# CORE.net
KiCad netlist of a schematic drawn in Altium Designer
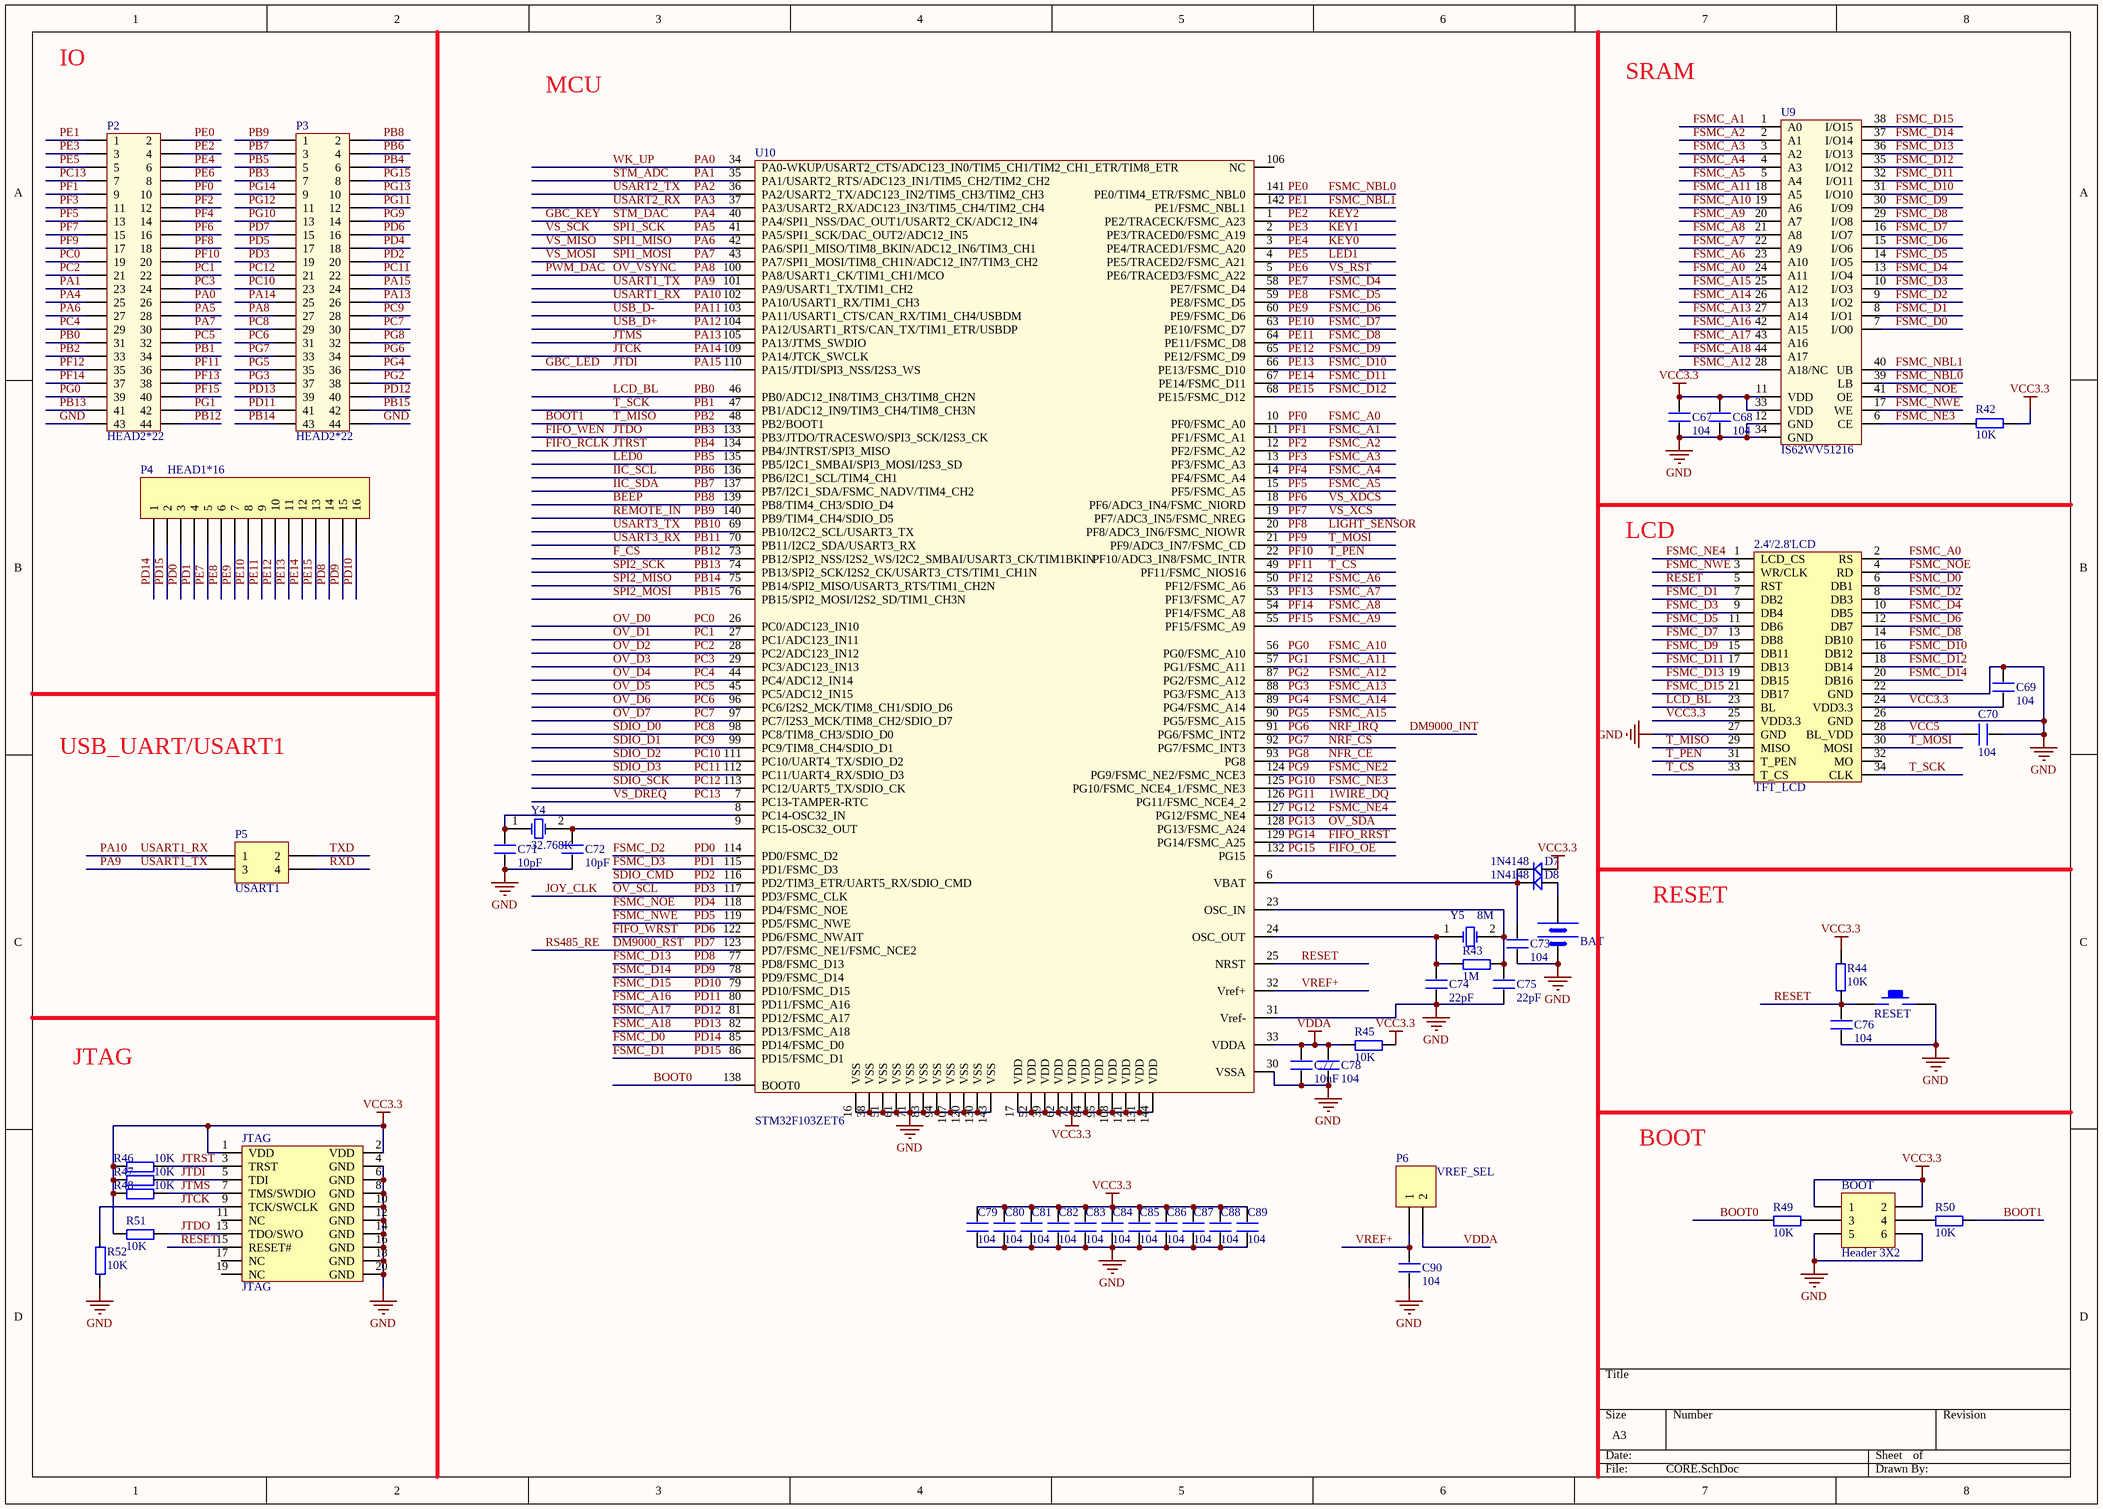
[diagram p0: CORE.SchDoc]

(export (version "E")
  (design (tool "Eeschema 10.0.6"))
  (components
    (comp (ref "2.4'/2.8'LCD")
      (value "TFT_LCD")
      (footprint "db2*17-4.3")
      (libsource (lib "WarShip V3 STM32103封装库") (part "TFT_LCD"))
    )
    (comp (ref "BAT")
      (value "BATT")
      (footprint "BATM")
      (libsource (lib "WarShip V3 STM32103封装库") (part "BAT"))
    )
    (comp (ref "BOOT")
      (value "Header 3X2")
      (footprint "HDR2X3")
      (description "Header, 3-Pin, Dual row")
      (fields (field (name "PUBLISHER") "Altium Limited"))
      (libsource (lib "WarShip V3 STM32103封装库") (part "Header 3X2"))
    )
    (comp (ref "C67") (value "104") (footprint "0603P") (libsource (lib "WarShip V3 STM32103封装库") (part "C")))
    (comp (ref "C68") (value "104") (footprint "0603P") (libsource (lib "WarShip V3 STM32103封装库") (part "C")))
    (comp (ref "C69") (value "104") (footprint "0603P") (libsource (lib "WarShip V3 STM32103封装库") (part "C")))
    (comp (ref "C70") (value "104") (footprint "0603P") (libsource (lib "WarShip V3 STM32103封装库") (part "C")))
    (comp (ref "C71")
      (value "10pF")
      (footprint "0603P")
      (libsource (lib "WarShip V3 STM32103封装库") (part "C"))
    )
    (comp (ref "C72")
      (value "10pF")
      (footprint "0603P")
      (libsource (lib "WarShip V3 STM32103封装库") (part "C"))
    )
    (comp (ref "C73") (value "104") (footprint "0603P") (libsource (lib "WarShip V3 STM32103封装库") (part "C")))
    (comp (ref "C74")
      (value "22pF")
      (footprint "0603P")
      (libsource (lib "WarShip V3 STM32103封装库") (part "C"))
    )
    (comp (ref "C75")
      (value "22pF")
      (footprint "0603P")
      (libsource (lib "WarShip V3 STM32103封装库") (part "C"))
    )
    (comp (ref "C76") (value "104") (footprint "0603P") (libsource (lib "WarShip V3 STM32103封装库") (part "C")))
    (comp (ref "C77")
      (value "10uF")
      (footprint "0603P")
      (libsource (lib "WarShip V3 STM32103封装库") (part "C"))
    )
    (comp (ref "C78") (value "104") (footprint "0603P") (libsource (lib "WarShip V3 STM32103封装库") (part "C")))
    (comp (ref "C79") (value "104") (footprint "0603P") (libsource (lib "WarShip V3 STM32103封装库") (part "C")))
    (comp (ref "C80") (value "104") (footprint "0603P") (libsource (lib "WarShip V3 STM32103封装库") (part "C")))
    (comp (ref "C81") (value "104") (footprint "0603P") (libsource (lib "WarShip V3 STM32103封装库") (part "C")))
    (comp (ref "C82") (value "104") (footprint "0603P") (libsource (lib "WarShip V3 STM32103封装库") (part "C")))
    (comp (ref "C83") (value "104") (footprint "0603P") (libsource (lib "WarShip V3 STM32103封装库") (part "C")))
    (comp (ref "C84") (value "104") (footprint "0603P") (libsource (lib "WarShip V3 STM32103封装库") (part "C")))
    (comp (ref "C85") (value "104") (footprint "0603P") (libsource (lib "WarShip V3 STM32103封装库") (part "C")))
    (comp (ref "C86") (value "104") (footprint "0603P") (libsource (lib "WarShip V3 STM32103封装库") (part "C")))
    (comp (ref "C87") (value "104") (footprint "0603P") (libsource (lib "WarShip V3 STM32103封装库") (part "C")))
    (comp (ref "C88") (value "104") (footprint "0603P") (libsource (lib "WarShip V3 STM32103封装库") (part "C")))
    (comp (ref "C89") (value "104") (footprint "0603P") (libsource (lib "WarShip V3 STM32103封装库") (part "C")))
    (comp (ref "C90") (value "104") (footprint "0603P") (libsource (lib "WarShip V3 STM32103封装库") (part "C")))
    (comp (ref "D7")
      (value "1N4148")
      (footprint "DIODE_SOP")
      (libsource (lib "WarShip V3 STM32103封装库") (part "D"))
    )
    (comp (ref "D8")
      (value "1N4148")
      (footprint "DIODE_SOP")
      (libsource (lib "WarShip V3 STM32103封装库") (part "D"))
    )
    (comp (ref "JTAG")
      (value "JTAG")
      (footprint "JTAG_20")
      (libsource (lib "WarShip V3 STM32103封装库") (part "JTAG"))
    )
    (comp (ref "P2")
      (value "HEAD2*22")
      (footprint "HEAD2*22")
      (libsource (lib "WarShip V3 STM32103封装库") (part "HEAD2*22"))
    )
    (comp (ref "P3")
      (value "HEAD2*22")
      (footprint "HEAD2*22")
      (libsource (lib "WarShip V3 STM32103封装库") (part "HEAD2*22"))
    )
    (comp (ref "P4")
      (value "HEAD1*16")
      (footprint "HDR1X16")
      (description "Header, 16-Pin")
      (fields (field (name "PUBLISHER") "Altium Limited"))
      (libsource (lib "WarShip V3 STM32103封装库") (part "Header 16"))
    )
    (comp (ref "P5")
      (value "USART1")
      (footprint "HDR2X2")
      (description "Header, 2-Pin, Dual row")
      (fields (field (name "PUBLISHER") "Altium Limited"))
      (libsource (lib "WarShip V3 STM32103封装库") (part "Header 2X2"))
    )
    (comp (ref "P6")
      (value "VREF_SEL")
      (footprint "HDR1X2")
      (description "Header, 2-Pin")
      (fields (field (name "PUBLISHER") "Altium Limited"))
      (libsource (lib "WarShip V3 STM32103封装库") (part "Header 2"))
    )
    (comp (ref "R42") (value "10K") (footprint "0603P") (libsource (lib "WarShip V3 STM32103封装库") (part "R")))
    (comp (ref "R43") (value "1M") (footprint "0603P") (libsource (lib "WarShip V3 STM32103封装库") (part "R")))
    (comp (ref "R44") (value "10K") (footprint "0603P") (libsource (lib "WarShip V3 STM32103封装库") (part "R")))
    (comp (ref "R45") (value "10K") (footprint "0603P") (libsource (lib "WarShip V3 STM32103封装库") (part "R")))
    (comp (ref "R46") (value "10K") (footprint "0603P") (libsource (lib "WarShip V3 STM32103封装库") (part "R")))
    (comp (ref "R47") (value "10K") (footprint "0603P") (libsource (lib "WarShip V3 STM32103封装库") (part "R")))
    (comp (ref "R48") (value "10K") (footprint "0603P") (libsource (lib "WarShip V3 STM32103封装库") (part "R")))
    (comp (ref "R49") (value "10K") (footprint "0603P") (libsource (lib "WarShip V3 STM32103封装库") (part "R")))
    (comp (ref "R50") (value "10K") (footprint "0603P") (libsource (lib "WarShip V3 STM32103封装库") (part "R")))
    (comp (ref "R51") (value "10K") (footprint "0603P") (libsource (lib "WarShip V3 STM32103封装库") (part "R")))
    (comp (ref "R52") (value "10K") (footprint "0603P") (libsource (lib "WarShip V3 STM32103封装库") (part "R")))
    (comp (ref "RESET")
      (value "KEY_M")
      (footprint "KEY_M")
      (libsource (lib "WarShip V3 STM32103封装库") (part "KEY_M"))
    )
    (comp (ref "U9")
      (value "IS62WV51216")
      (footprint "TSOP44")
      (libsource (lib "WarShip V3 STM32103封装库") (part "IS61LV51216"))
    )
    (comp (ref "U10")
      (value "STM32F103ZET6")
      (footprint "LQFP144")
      (libsource (lib "WarShip V3 STM32103封装库") (part "STM32F103ZET6"))
    )
    (comp (ref "Y4")
      (value "32.768K")
      (footprint "XTAL_US")
      (description "Crystal Oscillator")
      (fields (field (name "PUBLISHER") "Altium Limited"))
      (libsource (lib "WarShip V3 STM32103封装库") (part "XTAL"))
    )
    (comp (ref "Y5")
      (value "8M")
      (footprint "XTAL_US")
      (description "Crystal Oscillator")
      (fields (field (name "PUBLISHER") "Altium Limited"))
      (libsource (lib "WarShip V3 STM32103封装库") (part "XTAL"))
    )
  )
  (nets
    (net (code "1") (name "/1WIRE_DQ") (class "Default")
      (node (ref "P3") (pin "12") (pinfunction "12_12") (pintype "passive"))
      (node (ref "U10") (pin "126") (pinfunction "PG11/FSMC_NCE4_2_126") (pintype "passive"))
    )
    (net (code "2") (name "/BEEP") (class "Default")
      (node (ref "P3") (pin "2") (pinfunction "2_2") (pintype "passive"))
      (node (ref "U10") (pin "139") (pinfunction "PB8/TIM4_CH3/SDIO_D4_139") (pintype "passive"))
    )
    (net (code "3") (name "/BOOT0") (class "Default")
      (node (ref "R49") (pin "1") (pintype "passive"))
      (node (ref "U10") (pin "138") (pinfunction "BOOT0_138") (pintype "passive"))
    )
    (net (code "4") (name "/BOOT1") (class "Default")
      (node (ref "2.4'/2.8'LCD") (pin "29") (pinfunction "MISO_29") (pintype "passive"))
      (node (ref "P2") (pin "33") (pinfunction "33_33") (pintype "passive"))
      (node (ref "R50") (pin "2") (pintype "passive"))
      (node (ref "U10") (pin "48") (pinfunction "PB2/BOOT1_48") (pintype "passive"))
    )
    (net (code "5") (name "/DM9000_INT") (class "Default")
      (node (ref "P3") (pin "34") (pinfunction "34_34") (pintype "passive"))
      (node (ref "U10") (pin "91") (pinfunction "PG6/FSMC_INT2_91") (pintype "passive"))
    )
    (net (code "6") (name "/DM9000_RST") (class "Default")
      (node (ref "P3") (pin "15") (pinfunction "15_15") (pintype "passive"))
      (node (ref "U10") (pin "123") (pinfunction "PD7/FSMC_NE1/FSMC_NCE2_123") (pintype "passive"))
    )
    (net (code "7") (name "/FIFO_OE") (class "Default")
      (node (ref "P3") (pin "8") (pinfunction "8_8") (pintype "passive"))
      (node (ref "U10") (pin "132") (pinfunction "PG15_132") (pintype "passive"))
    )
    (net (code "8") (name "/FIFO_RCLK") (class "Default")
      (node (ref "JTAG") (pin "3") (pinfunction "TRST_3") (pintype "passive"))
      (node (ref "P3") (pin "6") (pinfunction "6_6") (pintype "passive"))
      (node (ref "R46") (pin "2") (pintype "passive"))
      (node (ref "U10") (pin "134") (pinfunction "PB4/JNTRST/SPI3_MISO_134") (pintype "passive"))
    )
    (net (code "9") (name "/FIFO_RRST") (class "Default")
      (node (ref "P3") (pin "9") (pinfunction "9_9") (pintype "passive"))
      (node (ref "U10") (pin "129") (pinfunction "PG14/FSMC_A25_129") (pintype "passive"))
    )
    (net (code "10") (name "/FIFO_WEN") (class "Default")
      (node (ref "JTAG") (pin "13") (pinfunction "TDO/SWO_13") (pintype "passive"))
      (node (ref "P3") (pin "7") (pinfunction "7_7") (pintype "passive"))
      (node (ref "R51") (pin "2") (pintype "passive"))
      (node (ref "U10") (pin "133") (pinfunction "PB3/JTDO/TRACESWO/SPI3_SCK/I2S3_CK_133") (pintype "passive"))
    )
    (net (code "11") (name "/FIFO_WRST") (class "Default")
      (node (ref "P3") (pin "16") (pinfunction "16_16") (pintype "passive"))
      (node (ref "U10") (pin "122") (pinfunction "PD6/FSMC_NWAIT_122") (pintype "passive"))
    )
    (net (code "12") (name "/FSMC_A0") (class "Default")
      (node (ref "2.4'/2.8'LCD") (pin "2") (pinfunction "RS_2") (pintype "passive"))
      (node (ref "P2") (pin "10") (pinfunction "10_10") (pintype "passive"))
      (node (ref "U10") (pin "10") (pinfunction "PF0/FSMC_A0_10") (pintype "passive"))
      (node (ref "U9") (pin "24") (pinfunction "A11_24") (pintype "passive"))
    )
    (net (code "13") (name "/FSMC_A1") (class "Default")
      (node (ref "P2") (pin "9") (pinfunction "9_9") (pintype "passive"))
      (node (ref "U10") (pin "11") (pinfunction "PF1/FSMC_A1_11") (pintype "passive"))
      (node (ref "U9") (pin "1") (pinfunction "A0_1") (pintype "passive"))
    )
    (net (code "14") (name "/FSMC_A2") (class "Default")
      (node (ref "P2") (pin "12") (pinfunction "12_12") (pintype "passive"))
      (node (ref "U10") (pin "12") (pinfunction "PF2/FSMC_A2_12") (pintype "passive"))
      (node (ref "U9") (pin "2") (pinfunction "A1_2") (pintype "passive"))
    )
    (net (code "15") (name "/FSMC_A3") (class "Default")
      (node (ref "P2") (pin "11") (pinfunction "11_11") (pintype "passive"))
      (node (ref "U10") (pin "13") (pinfunction "PF3/FSMC_A3_13") (pintype "passive"))
      (node (ref "U9") (pin "3") (pinfunction "A2_3") (pintype "passive"))
    )
    (net (code "16") (name "/FSMC_A4") (class "Default")
      (node (ref "P2") (pin "14") (pinfunction "14_14") (pintype "passive"))
      (node (ref "U10") (pin "14") (pinfunction "PF4/FSMC_A4_14") (pintype "passive"))
      (node (ref "U9") (pin "4") (pinfunction "A3_4") (pintype "passive"))
    )
    (net (code "17") (name "/FSMC_A5") (class "Default")
      (node (ref "P2") (pin "13") (pinfunction "13_13") (pintype "passive"))
      (node (ref "U10") (pin "15") (pinfunction "PF5/FSMC_A5_15") (pintype "passive"))
      (node (ref "U9") (pin "5") (pinfunction "A4_5") (pintype "passive"))
    )
    (net (code "18") (name "/FSMC_A6") (class "Default")
      (node (ref "P2") (pin "35") (pinfunction "35_35") (pintype "passive"))
      (node (ref "U10") (pin "50") (pinfunction "PF12/FSMC_A6_50") (pintype "passive"))
      (node (ref "U9") (pin "23") (pinfunction "A10_23") (pintype "passive"))
    )
    (net (code "19") (name "/FSMC_A7") (class "Default")
      (node (ref "P2") (pin "38") (pinfunction "38_38") (pintype "passive"))
      (node (ref "U10") (pin "53") (pinfunction "PF13/FSMC_A7_53") (pintype "passive"))
      (node (ref "U9") (pin "22") (pinfunction "A9_22") (pintype "passive"))
    )
    (net (code "20") (name "/FSMC_A8") (class "Default")
      (node (ref "P2") (pin "37") (pinfunction "37_37") (pintype "passive"))
      (node (ref "U10") (pin "54") (pinfunction "PF14/FSMC_A8_54") (pintype "passive"))
      (node (ref "U9") (pin "21") (pinfunction "A8_21") (pintype "passive"))
    )
    (net (code "21") (name "/FSMC_A9") (class "Default")
      (node (ref "P2") (pin "40") (pinfunction "40_40") (pintype "passive"))
      (node (ref "U10") (pin "55") (pinfunction "PF15/FSMC_A9_55") (pintype "passive"))
      (node (ref "U9") (pin "20") (pinfunction "A7_20") (pintype "passive"))
    )
    (net (code "22") (name "/FSMC_A10") (class "Default")
      (node (ref "P2") (pin "39") (pinfunction "39_39") (pintype "passive"))
      (node (ref "U10") (pin "56") (pinfunction "PG0/FSMC_A10_56") (pintype "passive"))
      (node (ref "U9") (pin "19") (pinfunction "A6_19") (pintype "passive"))
    )
    (net (code "23") (name "/FSMC_A11") (class "Default")
      (node (ref "P2") (pin "42") (pinfunction "42_42") (pintype "passive"))
      (node (ref "U10") (pin "57") (pinfunction "PG1/FSMC_A11_57") (pintype "passive"))
      (node (ref "U9") (pin "18") (pinfunction "A5_18") (pintype "passive"))
    )
    (net (code "24") (name "/FSMC_A12") (class "Default")
      (node (ref "P3") (pin "38") (pinfunction "38_38") (pintype "passive"))
      (node (ref "U10") (pin "87") (pinfunction "PG2/FSMC_A12_87") (pintype "passive"))
      (node (ref "U9") (pin "28") (pinfunction "A18/NC_28") (pintype "passive"))
    )
    (net (code "25") (name "/FSMC_A13") (class "Default")
      (node (ref "P3") (pin "37") (pinfunction "37_37") (pintype "passive"))
      (node (ref "U10") (pin "88") (pinfunction "PG3/FSMC_A13_88") (pintype "passive"))
      (node (ref "U9") (pin "27") (pinfunction "A14_27") (pintype "passive"))
    )
    (net (code "26") (name "/FSMC_A14") (class "Default")
      (node (ref "P3") (pin "36") (pinfunction "36_36") (pintype "passive"))
      (node (ref "U10") (pin "89") (pinfunction "PG4/FSMC_A14_89") (pintype "passive"))
      (node (ref "U9") (pin "26") (pinfunction "A13_26") (pintype "passive"))
    )
    (net (code "27") (name "/FSMC_A15") (class "Default")
      (node (ref "P3") (pin "35") (pinfunction "35_35") (pintype "passive"))
      (node (ref "U10") (pin "90") (pinfunction "PG5/FSMC_A15_90") (pintype "passive"))
      (node (ref "U9") (pin "25") (pinfunction "A12_25") (pintype "passive"))
    )
    (net (code "28") (name "/FSMC_A16") (class "Default")
      (node (ref "P3") (pin "41") (pinfunction "41_41") (pintype "passive"))
      (node (ref "U10") (pin "80") (pinfunction "PD11/FSMC_A16_80") (pintype "passive"))
      (node (ref "U9") (pin "42") (pinfunction "A15_42") (pintype "passive"))
    )
    (net (code "29") (name "/FSMC_A17") (class "Default")
      (node (ref "P3") (pin "40") (pinfunction "40_40") (pintype "passive"))
      (node (ref "U10") (pin "81") (pinfunction "PD12/FSMC_A17_81") (pintype "passive"))
      (node (ref "U9") (pin "43") (pinfunction "A16_43") (pintype "passive"))
    )
    (net (code "30") (name "/FSMC_A18") (class "Default")
      (node (ref "P3") (pin "39") (pinfunction "39_39") (pintype "passive"))
      (node (ref "U10") (pin "82") (pinfunction "PD13/FSMC_A18_82") (pintype "passive"))
      (node (ref "U9") (pin "44") (pinfunction "A17_44") (pintype "passive"))
    )
    (net (code "31") (name "/FSMC_D0") (class "Default")
      (node (ref "2.4'/2.8'LCD") (pin "6") (pinfunction "DB1_6") (pintype "passive"))
      (node (ref "P4") (pin "1") (pinfunction "1_1") (pintype "passive"))
      (node (ref "U10") (pin "85") (pinfunction "PD14/FSMC_D0_85") (pintype "passive"))
      (node (ref "U9") (pin "7") (pinfunction "I/O0_7") (pintype "passive"))
    )
    (net (code "32") (name "/FSMC_D1") (class "Default")
      (node (ref "2.4'/2.8'LCD") (pin "7") (pinfunction "DB2_7") (pintype "passive"))
      (node (ref "P4") (pin "2") (pinfunction "2_2") (pintype "passive"))
      (node (ref "U10") (pin "86") (pinfunction "PD15/FSMC_D1_86") (pintype "passive"))
      (node (ref "U9") (pin "8") (pinfunction "I/O1_8") (pintype "passive"))
    )
    (net (code "33") (name "/FSMC_D2") (class "Default")
      (node (ref "2.4'/2.8'LCD") (pin "8") (pinfunction "DB3_8") (pintype "passive"))
      (node (ref "P4") (pin "3") (pinfunction "3_3") (pintype "passive"))
      (node (ref "U10") (pin "114") (pinfunction "PD0/FSMC_D2_114") (pintype "passive"))
      (node (ref "U9") (pin "9") (pinfunction "I/O2_9") (pintype "passive"))
    )
    (net (code "34") (name "/FSMC_D3") (class "Default")
      (node (ref "2.4'/2.8'LCD") (pin "9") (pinfunction "DB4_9") (pintype "passive"))
      (node (ref "P4") (pin "4") (pinfunction "4_4") (pintype "passive"))
      (node (ref "U10") (pin "115") (pinfunction "PD1/FSMC_D3_115") (pintype "passive"))
      (node (ref "U9") (pin "10") (pinfunction "I/O3_10") (pintype "passive"))
    )
    (net (code "35") (name "/FSMC_D4") (class "Default")
      (node (ref "2.4'/2.8'LCD") (pin "10") (pinfunction "DB5_10") (pintype "passive"))
      (node (ref "P4") (pin "5") (pinfunction "5_5") (pintype "passive"))
      (node (ref "U10") (pin "58") (pinfunction "PE7/FSMC_D4_58") (pintype "passive"))
      (node (ref "U9") (pin "13") (pinfunction "I/O4_13") (pintype "passive"))
    )
    (net (code "36") (name "/FSMC_D5") (class "Default")
      (node (ref "2.4'/2.8'LCD") (pin "11") (pinfunction "DB6_11") (pintype "passive"))
      (node (ref "P4") (pin "6") (pinfunction "6_6") (pintype "passive"))
      (node (ref "U10") (pin "59") (pinfunction "PE8/FSMC_D5_59") (pintype "passive"))
      (node (ref "U9") (pin "14") (pinfunction "I/O5_14") (pintype "passive"))
    )
    (net (code "37") (name "/FSMC_D6") (class "Default")
      (node (ref "2.4'/2.8'LCD") (pin "12") (pinfunction "DB7_12") (pintype "passive"))
      (node (ref "P4") (pin "7") (pinfunction "7_7") (pintype "passive"))
      (node (ref "U10") (pin "60") (pinfunction "PE9/FSMC_D6_60") (pintype "passive"))
      (node (ref "U9") (pin "15") (pinfunction "I/O6_15") (pintype "passive"))
    )
    (net (code "38") (name "/FSMC_D7") (class "Default")
      (node (ref "2.4'/2.8'LCD") (pin "13") (pinfunction "DB8_13") (pintype "passive"))
      (node (ref "P4") (pin "8") (pinfunction "8_8") (pintype "passive"))
      (node (ref "U10") (pin "63") (pinfunction "PE10/FSMC_D7_63") (pintype "passive"))
      (node (ref "U9") (pin "16") (pinfunction "I/O7_16") (pintype "passive"))
    )
    (net (code "39") (name "/FSMC_D8") (class "Default")
      (node (ref "2.4'/2.8'LCD") (pin "14") (pinfunction "DB10_14") (pintype "passive"))
      (node (ref "P4") (pin "9") (pinfunction "9_9") (pintype "passive"))
      (node (ref "U10") (pin "64") (pinfunction "PE11/FSMC_D8_64") (pintype "passive"))
      (node (ref "U9") (pin "29") (pinfunction "I/O8_29") (pintype "passive"))
    )
    (net (code "40") (name "/FSMC_D9") (class "Default")
      (node (ref "2.4'/2.8'LCD") (pin "15") (pinfunction "DB11_15") (pintype "passive"))
      (node (ref "P4") (pin "10") (pinfunction "10_10") (pintype "passive"))
      (node (ref "U10") (pin "65") (pinfunction "PE12/FSMC_D9_65") (pintype "passive"))
      (node (ref "U9") (pin "30") (pinfunction "I/O9_30") (pintype "passive"))
    )
    (net (code "41") (name "/FSMC_D10") (class "Default")
      (node (ref "2.4'/2.8'LCD") (pin "16") (pinfunction "DB12_16") (pintype "passive"))
      (node (ref "P4") (pin "11") (pinfunction "11_11") (pintype "passive"))
      (node (ref "U10") (pin "66") (pinfunction "PE13/FSMC_D10_66") (pintype "passive"))
      (node (ref "U9") (pin "31") (pinfunction "I/O10_31") (pintype "passive"))
    )
    (net (code "42") (name "/FSMC_D11") (class "Default")
      (node (ref "2.4'/2.8'LCD") (pin "17") (pinfunction "DB13_17") (pintype "passive"))
      (node (ref "P4") (pin "12") (pinfunction "12_12") (pintype "passive"))
      (node (ref "U10") (pin "67") (pinfunction "PE14/FSMC_D11_67") (pintype "passive"))
      (node (ref "U9") (pin "32") (pinfunction "I/O11_32") (pintype "passive"))
    )
    (net (code "43") (name "/FSMC_D12") (class "Default")
      (node (ref "2.4'/2.8'LCD") (pin "18") (pinfunction "DB14_18") (pintype "passive"))
      (node (ref "P4") (pin "13") (pinfunction "13_13") (pintype "passive"))
      (node (ref "U10") (pin "68") (pinfunction "PE15/FSMC_D12_68") (pintype "passive"))
      (node (ref "U9") (pin "35") (pinfunction "I/O12_35") (pintype "passive"))
    )
    (net (code "44") (name "/FSMC_D13") (class "Default")
      (node (ref "2.4'/2.8'LCD") (pin "19") (pinfunction "DB15_19") (pintype "passive"))
      (node (ref "P4") (pin "14") (pinfunction "14_14") (pintype "passive"))
      (node (ref "U10") (pin "77") (pinfunction "PD8/FSMC_D13_77") (pintype "passive"))
      (node (ref "U9") (pin "36") (pinfunction "I/O13_36") (pintype "passive"))
    )
    (net (code "45") (name "/FSMC_D14") (class "Default")
      (node (ref "2.4'/2.8'LCD") (pin "20") (pinfunction "DB16_20") (pintype "passive"))
      (node (ref "P4") (pin "15") (pinfunction "15_15") (pintype "passive"))
      (node (ref "U10") (pin "78") (pinfunction "PD9/FSMC_D14_78") (pintype "passive"))
      (node (ref "U9") (pin "37") (pinfunction "I/O14_37") (pintype "passive"))
    )
    (net (code "46") (name "/FSMC_D15") (class "Default")
      (node (ref "2.4'/2.8'LCD") (pin "21") (pinfunction "DB17_21") (pintype "passive"))
      (node (ref "P4") (pin "16") (pinfunction "16_16") (pintype "passive"))
      (node (ref "U10") (pin "79") (pinfunction "PD10/FSMC_D15_79") (pintype "passive"))
      (node (ref "U9") (pin "38") (pinfunction "I/O15_38") (pintype "passive"))
    )
    (net (code "47") (name "/FSMC_NBL0") (class "Default")
      (node (ref "P2") (pin "2") (pinfunction "2_2") (pintype "passive"))
      (node (ref "U10") (pin "141") (pinfunction "PE0/TIM4_ETR/FSMC_NBL0_141") (pintype "passive"))
      (node (ref "U9") (pin "39") (pinfunction "LB_39") (pintype "passive"))
    )
    (net (code "48") (name "/FSMC_NBL1") (class "Default")
      (node (ref "P2") (pin "1") (pinfunction "1_1") (pintype "passive"))
      (node (ref "U10") (pin "142") (pinfunction "PE1/FSMC_NBL1_142") (pintype "passive"))
      (node (ref "U9") (pin "40") (pinfunction "UB_40") (pintype "passive"))
    )
    (net (code "49") (name "/FSMC_NE2") (class "Default")
      (node (ref "P3") (pin "14") (pinfunction "14_14") (pintype "passive"))
      (node (ref "U10") (pin "124") (pinfunction "PG9/FSMC_NE2/FSMC_NCE3_124") (pintype "passive"))
    )
    (net (code "50") (name "/FSMC_NE3") (class "Default")
      (node (ref "P3") (pin "13") (pinfunction "13_13") (pintype "passive"))
      (node (ref "R42") (pin "2") (pintype "passive"))
      (node (ref "U10") (pin "125") (pinfunction "PG10/FSMC_NCE4_1/FSMC_NE3_125") (pintype "passive"))
      (node (ref "U9") (pin "6") (pinfunction "CE_6") (pintype "passive"))
    )
    (net (code "51") (name "/FSMC_NE4") (class "Default")
      (node (ref "2.4'/2.8'LCD") (pin "1") (pinfunction "LCD_CS_1") (pintype "passive"))
      (node (ref "P3") (pin "11") (pinfunction "11_11") (pintype "passive"))
      (node (ref "U10") (pin "127") (pinfunction "PG12/FSMC_NE4_127") (pintype "passive"))
    )
    (net (code "52") (name "/FSMC_NOE") (class "Default")
      (node (ref "2.4'/2.8'LCD") (pin "4") (pinfunction "RD_4") (pintype "passive"))
      (node (ref "P3") (pin "18") (pinfunction "18_18") (pintype "passive"))
      (node (ref "U10") (pin "118") (pinfunction "PD4/FSMC_NOE_118") (pintype "passive"))
      (node (ref "U9") (pin "41") (pinfunction "OE_41") (pintype "passive"))
    )
    (net (code "53") (name "/FSMC_NWE") (class "Default")
      (node (ref "2.4'/2.8'LCD") (pin "3") (pinfunction "WR/CLK_3") (pintype "passive"))
      (node (ref "P3") (pin "17") (pinfunction "17_17") (pintype "passive"))
      (node (ref "U10") (pin "119") (pinfunction "PD5/FSMC_NWE_119") (pintype "passive"))
      (node (ref "U9") (pin "17") (pinfunction "WE_17") (pintype "passive"))
    )
    (net (code "54") (name "/F_CS") (class "Default")
      (node (ref "P2") (pin "44") (pinfunction "44_44") (pintype "passive"))
      (node (ref "U10") (pin "73") (pinfunction "PB12/SPI2_NSS/I2S2_WS/I2C2_SMBAI/USART3_CK/TIM1BKIN_73") (pintype "passive"))
    )
    (net (code "55") (name "/GBC_KEY") (class "Default")
      (node (ref "P2") (pin "25") (pinfunction "25_25") (pintype "passive"))
      (node (ref "U10") (pin "40") (pinfunction "PA4/SPI1_NSS/DAC_OUT1/USART2_CK/ADC12_IN4_40") (pintype "passive"))
    )
    (net (code "56") (name "/GBC_LED") (class "Default")
      (node (ref "JTAG") (pin "5") (pinfunction "TDI_5") (pintype "passive"))
      (node (ref "P3") (pin "24") (pinfunction "24_24") (pintype "passive"))
      (node (ref "R47") (pin "2") (pintype "passive"))
      (node (ref "U10") (pin "110") (pinfunction "PA15/JTDI/SPI3_NSS/I2S3_WS_110") (pintype "passive"))
    )
    (net (code "57") (name "/IIC_SCL") (class "Default")
      (node (ref "P3") (pin "4") (pinfunction "4_4") (pintype "passive"))
      (node (ref "U10") (pin "136") (pinfunction "PB6/I2C1_SCL/TIM4_CH1_136") (pintype "passive"))
    )
    (net (code "58") (name "/IIC_SDA") (class "Default")
      (node (ref "P3") (pin "3") (pinfunction "3_3") (pintype "passive"))
      (node (ref "U10") (pin "137") (pinfunction "PB7/I2C1_SDA/FSMC_NADV/TIM4_CH2_137") (pintype "passive"))
    )
    (net (code "59") (name "/JOY_CLK") (class "Default")
      (node (ref "P3") (pin "19") (pinfunction "19_19") (pintype "passive"))
      (node (ref "U10") (pin "117") (pinfunction "PD3/FSMC_CLK_117") (pintype "passive"))
    )
    (net (code "60") (name "/JTCK") (class "Default")
      (node (ref "JTAG") (pin "9") (pinfunction "TCK/SWCLK_9") (pintype "passive"))
      (node (ref "P3") (pin "25") (pinfunction "25_25") (pintype "passive"))
      (node (ref "R52") (pin "2") (pintype "passive"))
      (node (ref "U10") (pin "109") (pinfunction "PA14/JTCK_SWCLK_109") (pintype "passive"))
    )
    (net (code "61") (name "/JTMS") (class "Default")
      (node (ref "JTAG") (pin "7") (pinfunction "TMS/SWDIO_7") (pintype "passive"))
      (node (ref "P3") (pin "26") (pinfunction "26_26") (pintype "passive"))
      (node (ref "R48") (pin "2") (pintype "passive"))
      (node (ref "U10") (pin "105") (pinfunction "PA13/JTMS_SWDIO_105") (pintype "passive"))
    )
    (net (code "62") (name "/KEY0") (class "Default")
      (node (ref "P2") (pin "6") (pinfunction "6_6") (pintype "passive"))
      (node (ref "U10") (pin "3") (pinfunction "PE4/TRACED1/FSMC_A20_3") (pintype "passive"))
    )
    (net (code "63") (name "/KEY1") (class "Default")
      (node (ref "P2") (pin "3") (pinfunction "3_3") (pintype "passive"))
      (node (ref "U10") (pin "2") (pinfunction "PE3/TRACED0/FSMC_A19_2") (pintype "passive"))
    )
    (net (code "64") (name "/KEY2") (class "Default")
      (node (ref "P2") (pin "4") (pinfunction "4_4") (pintype "passive"))
      (node (ref "U10") (pin "1") (pinfunction "PE2/TRACECK/FSMC_A23_1") (pintype "passive"))
    )
    (net (code "65") (name "/LCD_BL") (class "Default")
      (node (ref "2.4'/2.8'LCD") (pin "23") (pinfunction "BL_23") (pintype "passive"))
      (node (ref "P2") (pin "31") (pinfunction "31_31") (pintype "passive"))
      (node (ref "U10") (pin "46") (pinfunction "PB0/ADC12_IN8/TIM3_CH3/TIM8_CH2N_46") (pintype "passive"))
    )
    (net (code "66") (name "/LED0") (class "Default")
      (node (ref "P3") (pin "5") (pinfunction "5_5") (pintype "passive"))
      (node (ref "U10") (pin "135") (pinfunction "PB5/I2C1_SMBAI/SPI3_MOSI/I2S3_SD_135") (pintype "passive"))
    )
    (net (code "67") (name "/LED1") (class "Default")
      (node (ref "P2") (pin "5") (pinfunction "5_5") (pintype "passive"))
      (node (ref "U10") (pin "4") (pinfunction "PE5/TRACED2/FSMC_A21_4") (pintype "passive"))
    )
    (net (code "68") (name "/LIGHT_SENSOR") (class "Default")
      (node (ref "P2") (pin "18") (pinfunction "18_18") (pintype "passive"))
      (node (ref "U10") (pin "20") (pinfunction "PF8/ADC3_IN6/FSMC_NIOWR_20") (pintype "passive"))
    )
    (net (code "69") (name "/NFR_CE") (class "Default")
      (node (ref "P3") (pin "32") (pinfunction "32_32") (pintype "passive"))
      (node (ref "U10") (pin "93") (pinfunction "PG8_93") (pintype "passive"))
    )
    (net (code "70") (name "/NRF_CS") (class "Default")
      (node (ref "P3") (pin "33") (pinfunction "33_33") (pintype "passive"))
      (node (ref "U10") (pin "92") (pinfunction "PG7/FSMC_INT3_92") (pintype "passive"))
    )
    (net (code "71") (name "/OV_D0") (class "Default")
      (node (ref "P2") (pin "19") (pinfunction "19_19") (pintype "passive"))
      (node (ref "U10") (pin "26") (pinfunction "PC0/ADC123_IN10_26") (pintype "passive"))
    )
    (net (code "72") (name "/OV_D1") (class "Default")
      (node (ref "P2") (pin "22") (pinfunction "22_22") (pintype "passive"))
      (node (ref "U10") (pin "27") (pinfunction "PC1/ADC123_IN11_27") (pintype "passive"))
    )
    (net (code "73") (name "/OV_D2") (class "Default")
      (node (ref "P2") (pin "21") (pinfunction "21_21") (pintype "passive"))
      (node (ref "U10") (pin "28") (pinfunction "PC2/ADC123_IN12_28") (pintype "passive"))
    )
    (net (code "74") (name "/OV_D3") (class "Default")
      (node (ref "P2") (pin "24") (pinfunction "24_24") (pintype "passive"))
      (node (ref "U10") (pin "29") (pinfunction "PC3/ADC123_IN13_29") (pintype "passive"))
    )
    (net (code "75") (name "/OV_D4") (class "Default")
      (node (ref "P2") (pin "29") (pinfunction "29_29") (pintype "passive"))
      (node (ref "U10") (pin "44") (pinfunction "PC4/ADC12_IN14_44") (pintype "passive"))
    )
    (net (code "76") (name "/OV_D5") (class "Default")
      (node (ref "P2") (pin "32") (pinfunction "32_32") (pintype "passive"))
      (node (ref "U10") (pin "45") (pinfunction "PC5/ADC12_IN15_45") (pintype "passive"))
    )
    (net (code "77") (name "/OV_D6") (class "Default")
      (node (ref "P3") (pin "31") (pinfunction "31_31") (pintype "passive"))
      (node (ref "U10") (pin "96") (pinfunction "PC6/I2S2_MCK/TIM8_CH1/SDIO_D6_96") (pintype "passive"))
    )
    (net (code "78") (name "/OV_D7") (class "Default")
      (node (ref "P3") (pin "30") (pinfunction "30_30") (pintype "passive"))
      (node (ref "U10") (pin "97") (pinfunction "PC7/I2S3_MCK/TIM8_CH2/SDIO_D7_97") (pintype "passive"))
    )
    (net (code "79") (name "/OV_SDA") (class "Default")
      (node (ref "P3") (pin "10") (pinfunction "10_10") (pintype "passive"))
      (node (ref "U10") (pin "128") (pinfunction "PG13/FSMC_A24_128") (pintype "passive"))
    )
    (net (code "80") (name "/OV_VSYNC") (class "Default")
      (node (ref "P3") (pin "27") (pinfunction "27_27") (pintype "passive"))
      (node (ref "U10") (pin "100") (pinfunction "PA8/USART1_CK/TIM1_CH1/MCO_100") (pintype "passive"))
    )
    (net (code "81") (name "/PA0") (class "Default")
      (node (ref "P2") (pin "26") (pinfunction "26_26") (pintype "passive"))
      (node (ref "U10") (pin "34") (pinfunction "PA0-WKUP/USART2_CTS/ADC123_IN0/TIM5_CH1/TIM2_CH1_ETR/TIM8_ETR_34") (pintype "passive"))
    )
    (net (code "82") (name "/PA1") (class "Default")
      (node (ref "P2") (pin "23") (pinfunction "23_23") (pintype "passive"))
      (node (ref "U10") (pin "35") (pinfunction "PA1/USART2_RTS/ADC123_IN1/TIM5_CH2/TIM2_CH2_35") (pintype "passive"))
    )
    (net (code "83") (name "/PA2") (class "Default")
      (node (ref "U10") (pin "36") (pinfunction "PA2/USART2_TX/ADC123_IN2/TIM5_CH3/TIM2_CH3_36") (pintype "passive"))
    )
    (net (code "84") (name "/PA3") (class "Default")
      (node (ref "U10") (pin "37") (pinfunction "PA3/USART2_RX/ADC123_IN3/TIM5_CH4/TIM2_CH4_37") (pintype "passive"))
    )
    (net (code "85") (name "/PA5") (class "Default")
      (node (ref "P2") (pin "28") (pinfunction "28_28") (pintype "passive"))
      (node (ref "U10") (pin "41") (pinfunction "PA5/SPI1_SCK/DAC_OUT2/ADC12_IN5_41") (pintype "passive"))
    )
    (net (code "86") (name "/PA6") (class "Default")
      (node (ref "P2") (pin "27") (pinfunction "27_27") (pintype "passive"))
      (node (ref "U10") (pin "42") (pinfunction "PA6/SPI1_MISO/TIM8_BKIN/ADC12_IN6/TIM3_CH1_42") (pintype "passive"))
    )
    (net (code "87") (name "/PA7") (class "Default")
      (node (ref "P2") (pin "30") (pinfunction "30_30") (pintype "passive"))
      (node (ref "U10") (pin "43") (pinfunction "PA7/SPI1_MOSI/TIM8_CH1N/ADC12_IN7/TIM3_CH2_43") (pintype "passive"))
    )
    (net (code "88") (name "/PA9") (class "Default")
      (node (ref "P5") (pin "3") (pinfunction "3_3") (pintype "passive"))
      (node (ref "U10") (pin "101") (pinfunction "PA9/USART1_TX/TIM1_CH2_101") (pintype "passive"))
    )
    (net (code "89") (name "/PA10") (class "Default")
      (node (ref "P5") (pin "1") (pinfunction "1_1") (pintype "passive"))
      (node (ref "U10") (pin "102") (pinfunction "PA10/USART1_RX/TIM1_CH3_102") (pintype "passive"))
    )
    (net (code "90") (name "/PA11") (class "Default")
      (node (ref "U10") (pin "103") (pinfunction "PA11/USART1_CTS/CAN_RX/TIM1_CH4/USBDM_103") (pintype "passive"))
    )
    (net (code "91") (name "/PA12") (class "Default")
      (node (ref "U10") (pin "104") (pinfunction "PA12/USART1_RTS/CAN_TX/TIM1_ETR/USBDP_104") (pintype "passive"))
    )
    (net (code "92") (name "/PB1") (class "Default")
      (node (ref "2.4'/2.8'LCD") (pin "34") (pinfunction "CLK_34") (pintype "passive"))
      (node (ref "P2") (pin "34") (pinfunction "34_34") (pintype "passive"))
      (node (ref "U10") (pin "47") (pinfunction "PB1/ADC12_IN9/TIM3_CH4/TIM8_CH3N_47") (pintype "passive"))
    )
    (net (code "93") (name "/PB9") (class "Default")
      (node (ref "P3") (pin "1") (pinfunction "1_1") (pintype "passive"))
      (node (ref "U10") (pin "140") (pinfunction "PB9/TIM4_CH4/SDIO_D5_140") (pintype "passive"))
    )
    (net (code "94") (name "/PB10") (class "Default")
      (node (ref "U10") (pin "69") (pinfunction "PB10/I2C2_SCL/USART3_TX_69") (pintype "passive"))
    )
    (net (code "95") (name "/PB11") (class "Default")
      (node (ref "U10") (pin "70") (pinfunction "PB11/I2C2_SDA/USART3_RX_70") (pintype "passive"))
    )
    (net (code "96") (name "/PB13") (class "Default")
      (node (ref "P2") (pin "41") (pinfunction "41_41") (pintype "passive"))
      (node (ref "U10") (pin "74") (pinfunction "PB13/SPI2_SCK/I2S2_CK/USART3_CTS/TIM1_CH1N_74") (pintype "passive"))
    )
    (net (code "97") (name "/PB14") (class "Default")
      (node (ref "P3") (pin "43") (pinfunction "43_43") (pintype "passive"))
      (node (ref "U10") (pin "75") (pinfunction "PB14/SPI2_MISO/USART3_RTS/TIM1_CH2N_75") (pintype "passive"))
    )
    (net (code "98") (name "/PB15") (class "Default")
      (node (ref "P3") (pin "42") (pinfunction "42_42") (pintype "passive"))
      (node (ref "U10") (pin "76") (pinfunction "PB15/SPI2_MOSI/I2S2_SD/TIM1_CH3N_76") (pintype "passive"))
    )
    (net (code "99") (name "/PC8") (class "Default")
      (node (ref "P3") (pin "29") (pinfunction "29_29") (pintype "passive"))
      (node (ref "U10") (pin "98") (pinfunction "PC8/TIM8_CH3/SDIO_D0_98") (pintype "passive"))
    )
    (net (code "100") (name "/PC9") (class "Default")
      (node (ref "P3") (pin "28") (pinfunction "28_28") (pintype "passive"))
      (node (ref "U10") (pin "99") (pinfunction "PC9/TIM8_CH4/SDIO_D1_99") (pintype "passive"))
    )
    (net (code "101") (name "/PC10") (class "Default")
      (node (ref "P3") (pin "23") (pinfunction "23_23") (pintype "passive"))
      (node (ref "U10") (pin "111") (pinfunction "PC10/UART4_TX/SDIO_D2_111") (pintype "passive"))
    )
    (net (code "102") (name "/PC11") (class "Default")
      (node (ref "P3") (pin "22") (pinfunction "22_22") (pintype "passive"))
      (node (ref "U10") (pin "112") (pinfunction "PC11/UART4_RX/SDIO_D3_112") (pintype "passive"))
    )
    (net (code "103") (name "/PC12") (class "Default")
      (node (ref "P3") (pin "21") (pinfunction "21_21") (pintype "passive"))
      (node (ref "U10") (pin "113") (pinfunction "PC12/UART5_TX/SDIO_CK_113") (pintype "passive"))
    )
    (net (code "104") (name "/PC13") (class "Default")
      (node (ref "P2") (pin "7") (pinfunction "7_7") (pintype "passive"))
      (node (ref "U10") (pin "7") (pinfunction "PC13-TAMPER-RTC_7") (pintype "passive"))
    )
    (net (code "105") (name "/PD2") (class "Default")
      (node (ref "P3") (pin "20") (pinfunction "20_20") (pintype "passive"))
      (node (ref "U10") (pin "116") (pinfunction "PD2/TIM3_ETR/UART5_RX/SDIO_CMD_116") (pintype "passive"))
    )
    (net (code "106") (name "/PE6") (class "Default")
      (node (ref "P2") (pin "8") (pinfunction "8_8") (pintype "passive"))
      (node (ref "U10") (pin "5") (pinfunction "PE6/TRACED3/FSMC_A22_5") (pintype "passive"))
    )
    (net (code "107") (name "/PF6") (class "Default")
      (node (ref "P2") (pin "16") (pinfunction "16_16") (pintype "passive"))
      (node (ref "U10") (pin "18") (pinfunction "PF6/ADC3_IN4/FSMC_NIORD_18") (pintype "passive"))
    )
    (net (code "108") (name "/PF7") (class "Default")
      (node (ref "P2") (pin "15") (pinfunction "15_15") (pintype "passive"))
      (node (ref "U10") (pin "19") (pinfunction "PF7/ADC3_IN5/FSMC_NREG_19") (pintype "passive"))
    )
    (net (code "109") (name "/PF9") (class "Default")
      (node (ref "2.4'/2.8'LCD") (pin "30") (pinfunction "MOSI_30") (pintype "passive"))
      (node (ref "P2") (pin "17") (pinfunction "17_17") (pintype "passive"))
      (node (ref "U10") (pin "21") (pinfunction "PF9/ADC3_IN7/FSMC_CD_21") (pintype "passive"))
    )
    (net (code "110") (name "/PF10") (class "Default")
      (node (ref "2.4'/2.8'LCD") (pin "31") (pinfunction "T_PEN_31") (pintype "passive"))
      (node (ref "P2") (pin "20") (pinfunction "20_20") (pintype "passive"))
      (node (ref "U10") (pin "22") (pinfunction "PF10/ADC3_IN8/FSMC_INTR_22") (pintype "passive"))
    )
    (net (code "111") (name "/PF11") (class "Default")
      (node (ref "2.4'/2.8'LCD") (pin "33") (pinfunction "T_CS_33") (pintype "passive"))
      (node (ref "P2") (pin "36") (pinfunction "36_36") (pintype "passive"))
      (node (ref "U10") (pin "49") (pinfunction "PF11/FSMC_NIOS16_49") (pintype "passive"))
    )
    (net (code "112") (name "/RESET") (class "Default")
      (node (ref "2.4'/2.8'LCD") (pin "5") (pinfunction "RST_5") (pintype "passive"))
      (node (ref "C76") (pin "1") (pintype "passive"))
      (node (ref "JTAG") (pin "15") (pinfunction "RESET#_15") (pintype "passive"))
      (node (ref "R44") (pin "2") (pintype "passive"))
      (node (ref "RESET") (pin "1") (pinfunction "1_1") (pintype "passive"))
      (node (ref "U10") (pin "25") (pinfunction "NRST_25") (pintype "passive"))
    )
    (net (code "113") (name "/RXD") (class "Default")
      (node (ref "P5") (pin "4") (pinfunction "4_4") (pintype "passive"))
    )
    (net (code "114") (name "/TXD") (class "Default")
      (node (ref "P5") (pin "2") (pinfunction "2_2") (pintype "passive"))
    )
    (net (code "115") (name "/VCC5") (class "Default")
      (node (ref "2.4'/2.8'LCD") (pin "28") (pinfunction "BL_VDD_28") (pintype "passive"))
      (node (ref "C70") (pin "2") (pintype "passive"))
    )
    (net (code "116") (name "/VREF+") (class "Default")
      (node (ref "C90") (pin "1") (pintype "passive"))
      (node (ref "P6") (pin "1") (pinfunction "1_1") (pintype "passive"))
      (node (ref "U10") (pin "32") (pinfunction "Vref+_32") (pintype "passive"))
    )
    (net (code "117") (name "GND") (class "Default")
      (node (ref "2.4'/2.8'LCD") (pin "22") (pinfunction "GND_22") (pintype "passive"))
      (node (ref "2.4'/2.8'LCD") (pin "26") (pinfunction "GND_26") (pintype "passive"))
      (node (ref "2.4'/2.8'LCD") (pin "27") (pinfunction "GND_27") (pintype "passive"))
      (node (ref "BAT") (pin "2") (pinfunction "GND_2") (pintype "passive"))
      (node (ref "BOOT") (pin "5") (pinfunction "5_5") (pintype "passive"))
      (node (ref "BOOT") (pin "6") (pinfunction "6_6") (pintype "passive"))
      (node (ref "C67") (pin "1") (pintype "passive"))
      (node (ref "C68") (pin "1") (pintype "passive"))
      (node (ref "C69") (pin "1") (pintype "passive"))
      (node (ref "C70") (pin "1") (pintype "passive"))
      (node (ref "C71") (pin "2") (pintype "passive"))
      (node (ref "C72") (pin "2") (pintype "passive"))
      (node (ref "C73") (pin "2") (pintype "passive"))
      (node (ref "C74") (pin "2") (pintype "passive"))
      (node (ref "C75") (pin "2") (pintype "passive"))
      (node (ref "C76") (pin "2") (pintype "passive"))
      (node (ref "C77") (pin "2") (pintype "passive"))
      (node (ref "C78") (pin "2") (pintype "passive"))
      (node (ref "C79") (pin "2") (pintype "passive"))
      (node (ref "C80") (pin "2") (pintype "passive"))
      (node (ref "C81") (pin "2") (pintype "passive"))
      (node (ref "C82") (pin "2") (pintype "passive"))
      (node (ref "C83") (pin "2") (pintype "passive"))
      (node (ref "C84") (pin "2") (pintype "passive"))
      (node (ref "C85") (pin "2") (pintype "passive"))
      (node (ref "C86") (pin "2") (pintype "passive"))
      (node (ref "C87") (pin "2") (pintype "passive"))
      (node (ref "C88") (pin "2") (pintype "passive"))
      (node (ref "C89") (pin "2") (pintype "passive"))
      (node (ref "C90") (pin "2") (pintype "passive"))
      (node (ref "JTAG") (pin "10") (pinfunction "GND_10") (pintype "passive"))
      (node (ref "JTAG") (pin "12") (pinfunction "GND_12") (pintype "passive"))
      (node (ref "JTAG") (pin "14") (pinfunction "GND_14") (pintype "passive"))
      (node (ref "JTAG") (pin "16") (pinfunction "GND_16") (pintype "passive"))
      (node (ref "JTAG") (pin "18") (pinfunction "GND_18") (pintype "passive"))
      (node (ref "JTAG") (pin "20") (pinfunction "GND_20") (pintype "passive"))
      (node (ref "JTAG") (pin "4") (pinfunction "GND_4") (pintype "passive"))
      (node (ref "JTAG") (pin "6") (pinfunction "GND_6") (pintype "passive"))
      (node (ref "JTAG") (pin "8") (pinfunction "GND_8") (pintype "passive"))
      (node (ref "P2") (pin "43") (pinfunction "43_43") (pintype "passive"))
      (node (ref "P3") (pin "44") (pinfunction "44_44") (pintype "passive"))
      (node (ref "R52") (pin "1") (pintype "passive"))
      (node (ref "RESET") (pin "2") (pinfunction "2_2") (pintype "passive"))
      (node (ref "U10") (pin "107") (pinfunction "VSS_107") (pintype "passive"))
      (node (ref "U10") (pin "120") (pinfunction "VSS_120") (pintype "passive"))
      (node (ref "U10") (pin "130") (pinfunction "VSS_130") (pintype "passive"))
      (node (ref "U10") (pin "143") (pinfunction "VSS_143") (pintype "passive"))
      (node (ref "U10") (pin "16") (pinfunction "VSS_16") (pintype "passive"))
      (node (ref "U10") (pin "30") (pinfunction "VSSA_30") (pintype "passive"))
      (node (ref "U10") (pin "31") (pinfunction "Vref-_31") (pintype "passive"))
      (node (ref "U10") (pin "38") (pinfunction "VSS_38") (pintype "passive"))
      (node (ref "U10") (pin "51") (pinfunction "VSS_51") (pintype "passive"))
      (node (ref "U10") (pin "61") (pinfunction "VSS_61") (pintype "passive"))
      (node (ref "U10") (pin "71") (pinfunction "VSS_71") (pintype "passive"))
      (node (ref "U10") (pin "83") (pinfunction "VSS_83") (pintype "passive"))
      (node (ref "U10") (pin "94") (pinfunction "VSS_94") (pintype "passive"))
      (node (ref "U9") (pin "12") (pinfunction "GND_12") (pintype "passive"))
      (node (ref "U9") (pin "34") (pinfunction "GND_34") (pintype "passive"))
    )
    (net (code "118") (name "Net-(BAT-VCC)") (class "Default")
      (node (ref "BAT") (pin "1") (pinfunction "VCC_1") (pintype "passive"))
      (node (ref "D8") (pin "1") (pintype "passive"))
    )
    (net (code "119") (name "Net-(BOOT-Pad3)") (class "Default")
      (node (ref "BOOT") (pin "3") (pinfunction "3_3") (pintype "passive"))
      (node (ref "R49") (pin "2") (pintype "passive"))
    )
    (net (code "120") (name "Net-(BOOT-Pad4)") (class "Default")
      (node (ref "BOOT") (pin "4") (pinfunction "4_4") (pintype "passive"))
      (node (ref "R50") (pin "1") (pintype "passive"))
    )
    (net (code "121") (name "Net-(U10-OSC_IN)") (class "Default")
      (node (ref "C75") (pin "1") (pintype "passive"))
      (node (ref "R43") (pin "2") (pintype "passive"))
      (node (ref "U10") (pin "23") (pinfunction "OSC_IN_23") (pintype "passive"))
      (node (ref "Y5") (pin "2") (pinfunction "OSC2_2") (pintype "passive"))
    )
    (net (code "122") (name "Net-(U10-OSC_OUT)") (class "Default")
      (node (ref "C74") (pin "1") (pintype "passive"))
      (node (ref "R43") (pin "1") (pintype "passive"))
      (node (ref "U10") (pin "24") (pinfunction "OSC_OUT_24") (pintype "passive"))
      (node (ref "Y5") (pin "1") (pinfunction "OSC1_1") (pintype "passive"))
    )
    (net (code "123") (name "Net-(U10-PC14-OSC32_IN)") (class "Default")
      (node (ref "C71") (pin "1") (pintype "passive"))
      (node (ref "U10") (pin "8") (pinfunction "PC14-OSC32_IN_8") (pintype "passive"))
      (node (ref "Y4") (pin "1") (pinfunction "OSC1_1") (pintype "passive"))
    )
    (net (code "124") (name "Net-(U10-PC15-OSC32_OUT)") (class "Default")
      (node (ref "C72") (pin "1") (pintype "passive"))
      (node (ref "U10") (pin "9") (pinfunction "PC15-OSC32_OUT_9") (pintype "passive"))
      (node (ref "Y4") (pin "2") (pinfunction "OSC2_2") (pintype "passive"))
    )
    (net (code "125") (name "Net-(U10-VBAT)") (class "Default")
      (node (ref "C73") (pin "1") (pintype "passive"))
      (node (ref "D7") (pin "2") (pintype "passive"))
      (node (ref "D8") (pin "2") (pintype "passive"))
      (node (ref "U10") (pin "6") (pinfunction "VBAT_6") (pintype "passive"))
    )
    (net (code "126") (name "VCC3.3") (class "Default")
      (node (ref "2.4'/2.8'LCD") (pin "24") (pinfunction "VDD3.3_24") (pintype "passive"))
      (node (ref "2.4'/2.8'LCD") (pin "25") (pinfunction "VDD3.3_25") (pintype "passive"))
      (node (ref "BOOT") (pin "1") (pinfunction "1_1") (pintype "passive"))
      (node (ref "BOOT") (pin "2") (pinfunction "2_2") (pintype "passive"))
      (node (ref "C67") (pin "2") (pintype "passive"))
      (node (ref "C68") (pin "2") (pintype "passive"))
      (node (ref "C69") (pin "2") (pintype "passive"))
      (node (ref "C79") (pin "1") (pintype "passive"))
      (node (ref "C80") (pin "1") (pintype "passive"))
      (node (ref "C81") (pin "1") (pintype "passive"))
      (node (ref "C82") (pin "1") (pintype "passive"))
      (node (ref "C83") (pin "1") (pintype "passive"))
      (node (ref "C84") (pin "1") (pintype "passive"))
      (node (ref "C85") (pin "1") (pintype "passive"))
      (node (ref "C86") (pin "1") (pintype "passive"))
      (node (ref "C87") (pin "1") (pintype "passive"))
      (node (ref "C88") (pin "1") (pintype "passive"))
      (node (ref "C89") (pin "1") (pintype "passive"))
      (node (ref "D7") (pin "1") (pintype "passive"))
      (node (ref "JTAG") (pin "1") (pinfunction "VDD_1") (pintype "passive"))
      (node (ref "JTAG") (pin "2") (pinfunction "VDD_2") (pintype "passive"))
      (node (ref "R42") (pin "1") (pintype "passive"))
      (node (ref "R44") (pin "1") (pintype "passive"))
      (node (ref "R45") (pin "2") (pintype "passive"))
      (node (ref "R46") (pin "1") (pintype "passive"))
      (node (ref "R47") (pin "1") (pintype "passive"))
      (node (ref "R48") (pin "1") (pintype "passive"))
      (node (ref "R51") (pin "1") (pintype "passive"))
      (node (ref "U10") (pin "108") (pinfunction "VDD_108") (pintype "passive"))
      (node (ref "U10") (pin "121") (pinfunction "VDD_121") (pintype "passive"))
      (node (ref "U10") (pin "131") (pinfunction "VDD_131") (pintype "passive"))
      (node (ref "U10") (pin "144") (pinfunction "VDD_144") (pintype "passive"))
      (node (ref "U10") (pin "17") (pinfunction "VDD_17") (pintype "passive"))
      (node (ref "U10") (pin "39") (pinfunction "VDD_39") (pintype "passive"))
      (node (ref "U10") (pin "52") (pinfunction "VDD_52") (pintype "passive"))
      (node (ref "U10") (pin "62") (pinfunction "VDD_62") (pintype "passive"))
      (node (ref "U10") (pin "72") (pinfunction "VDD_72") (pintype "passive"))
      (node (ref "U10") (pin "84") (pinfunction "VDD_84") (pintype "passive"))
      (node (ref "U10") (pin "95") (pinfunction "VDD_95") (pintype "passive"))
      (node (ref "U9") (pin "11") (pinfunction "VDD_11") (pintype "passive"))
      (node (ref "U9") (pin "33") (pinfunction "VDD_33") (pintype "passive"))
    )
    (net (code "127") (name "VDDA") (class "Default")
      (node (ref "C77") (pin "1") (pintype "passive"))
      (node (ref "C78") (pin "1") (pintype "passive"))
      (node (ref "P6") (pin "2") (pinfunction "2_2") (pintype "passive"))
      (node (ref "R45") (pin "1") (pintype "passive"))
      (node (ref "U10") (pin "33") (pinfunction "VDDA_33") (pintype "passive"))
    )
    (net (code "128") (name "unconnected-(2.4'/2.8'LCD-MO-Pad32)") (class "Default")
      (node (ref "2.4'/2.8'LCD") (pin "32") (pinfunction "MO_32") (pintype "passive"))
    )
    (net (code "129") (name "unconnected-(JTAG-NC-Pad11)") (class "Default")
      (node (ref "JTAG") (pin "11") (pinfunction "NC_11") (pintype "passive"))
    )
    (net (code "130") (name "unconnected-(JTAG-NC-Pad17)") (class "Default")
      (node (ref "JTAG") (pin "17") (pinfunction "NC_17") (pintype "passive"))
    )
    (net (code "131") (name "unconnected-(JTAG-NC-Pad19)") (class "Default")
      (node (ref "JTAG") (pin "19") (pinfunction "NC_19") (pintype "passive"))
    )
    (net (code "132") (name "unconnected-(U10-NC-Pad106)") (class "Default")
      (node (ref "U10") (pin "106") (pinfunction "NC_106") (pintype "passive"))
    )
  )
)
